# CoilDriver.net
KiCad netlist of a schematic drawn in Altium Designer
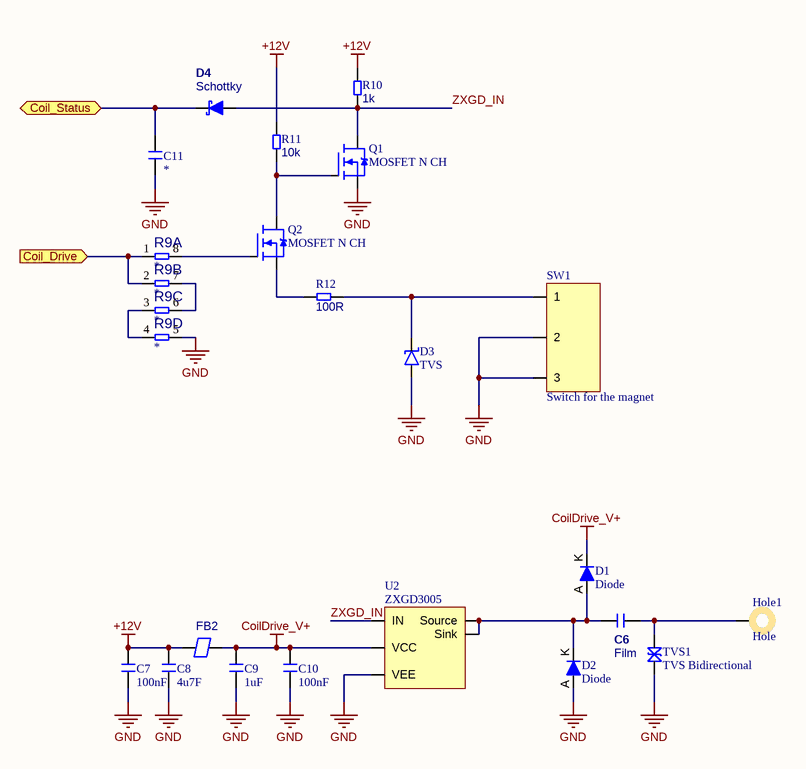
[diagram p0: CoilDriver.SchDoc]

(export (version "E")
  (design (tool "Eeschema 10.0.6"))
  (components
    (comp (ref "C6")
      (value "Film")
      (footprint "Cap Film 5mm pitch, 7.2x7.2mm")
      (libsource (lib "wes") (part "Capacitor - Film"))
    )
    (comp (ref "C7")
      (value "100nF")
      (footprint "C0603_N")
      (description "Capacitor MLCC")
      (fields
        (field (name "MANUFACTURER") "Yageo")
        (field (name "MANUFACTURER PART NUMBER") "CC0603KRX7R9BB104")
      )
      (libsource (lib "wes") (part "Capacitor"))
    )
    (comp (ref "C8")
      (value "4u7F")
      (footprint "C1206_N")
      (description "Capacitor MLCC")
      (fields
        (field (name "MANUFACTURER") "Yageo")
        (field (name "MANUFACTURER PART NUMBER") "CC0603KRX7R9BB104")
      )
      (libsource (lib "wes") (part "Capacitor"))
    )
    (comp (ref "C9")
      (value "1uF")
      (footprint "C0603_N")
      (description "Capacitor MLCC")
      (fields
        (field (name "MANUFACTURER") "Yageo")
        (field (name "MANUFACTURER PART NUMBER") "CC0603KRX7R9BB104")
      )
      (libsource (lib "wes") (part "Capacitor"))
    )
    (comp (ref "C10")
      (value "100nF")
      (footprint "C0603_N")
      (description "Capacitor MLCC")
      (fields
        (field (name "MANUFACTURER") "Yageo")
        (field (name "MANUFACTURER PART NUMBER") "CC0603KRX7R9BB104")
      )
      (libsource (lib "wes") (part "Capacitor"))
    )
    (comp (ref "C11")
      (value "*")
      (footprint "C0603_N")
      (description "Capacitor MLCC")
      (fields
        (field (name "MANUFACTURER") "Yageo")
        (field (name "MANUFACTURER PART NUMBER") "CC0603KRX7R9BB104")
      )
      (libsource (lib "wes") (part "Capacitor"))
    )
    (comp (ref "D1") (value "Diode") (footprint "SOD323F") (libsource (lib "wes") (part "Diode")))
    (comp (ref "D2") (value "Diode") (footprint "SOD323F") (libsource (lib "wes") (part "Diode")))
    (comp (ref "D3") (value "TVS") (footprint "SOD323F-Comchip Variant") (libsource (lib "wes") (part "TVS")))
    (comp (ref "D4") (value "Schottky") (footprint "SOD323F") (libsource (lib "wes") (part "Diode Schottky")))
    (comp (ref "FB2")
      (value "Ferrite Bead")
      (footprint "F0603_N")
      (libsource (lib "wes") (part "Ferrite Bead"))
    )
    (comp (ref "Hole1")
      (value "Hole")
      (footprint "Insert-Thread-SMD-M2")
      (libsource (lib "wes") (part "Hole"))
    )
    (comp (ref "Q1") (value "MOSFET N CH") (footprint "SOT23_N") (libsource (lib "wes") (part "MOSFET N CH")))
    (comp (ref "Q2") (value "MOSFET N CH") (footprint "SOT23_N") (libsource (lib "wes") (part "MOSFET N CH")))
    (comp (ref "R9")
      (value "Resistor Array - 4P")
      (footprint "YC164")
      (fields (field (name "ALTIUM_VALUE") "*"))
      (libsource (lib "wes") (part "Resistor Array - 4P"))
    )
    (comp (ref "R10")
      (value "1k")
      (footprint "R0603")
      (fields (field (name "Comment") "Resistor") (field (name "PUBLISHER") "Altium Limited"))
      (libsource (lib "wes") (part "Resistor"))
    )
    (comp (ref "R11")
      (value "10k")
      (footprint "R0603")
      (fields (field (name "Comment") "Resistor") (field (name "PUBLISHER") "Altium Limited"))
      (libsource (lib "wes") (part "Resistor"))
    )
    (comp (ref "R12")
      (value "100R")
      (footprint "R0603")
      (fields (field (name "Comment") "Resistor") (field (name "PUBLISHER") "Altium Limited"))
      (libsource (lib "wes") (part "Resistor"))
    )
    (comp (ref "SW1")
      (value "Switch for the magnet")
      (footprint "Linobyte - MagnetSwitch")
      (libsource (lib "wes") (part "Linobyte - MagnetSwitch"))
    )
    (comp (ref "TVS1")
      (value "TVS Bidirectional")
      (footprint "DO214AC SMA")
      (libsource (lib "wes") (part "TVS Bidirectional"))
    )
    (comp (ref "U2") (value "ZXGD3005") (footprint "SOT23-6_N") (libsource (lib "wes") (part "ZXGD3005")))
  )
  (nets
    (net (code "1") (name "+12V") (class "Default")
      (node (ref "C7") (pin "1") (pintype "passive"))
      (node (ref "C8") (pin "1") (pintype "passive"))
      (node (ref "FB2") (pin "2") (pinfunction "2_2") (pintype "passive"))
      (node (ref "R10") (pin "2") (pinfunction "2_2") (pintype "passive"))
      (node (ref "R11") (pin "2") (pinfunction "2_2") (pintype "passive"))
    )
    (net (code "2") (name "/Coil_Drive") (class "Default")
      (node (ref "R9") (pin "1") (pinfunction "1_1") (pintype "passive"))
      (node (ref "R9") (pin "2") (pinfunction "2_2") (pintype "passive"))
    )
    (net (code "3") (name "/Coil_Status") (class "Default")
      (node (ref "C11") (pin "1") (pintype "passive"))
      (node (ref "D4") (pin "K") (pinfunction "K_K") (pintype "passive"))
    )
    (net (code "4") (name "/ZXGD_IN") (class "Default")
      (node (ref "D4") (pin "A") (pinfunction "A_A") (pintype "passive"))
      (node (ref "Q1") (pin "2") (pinfunction "D_2") (pintype "passive"))
      (node (ref "R10") (pin "1") (pinfunction "1_1") (pintype "passive"))
      (node (ref "U2") (pin "2") (pinfunction "IN_2") (pintype "passive"))
    )
    (net (code "5") (name "CoilDrive_V+") (class "Default")
      (node (ref "C10") (pin "1") (pintype "passive"))
      (node (ref "C9") (pin "1") (pintype "passive"))
      (node (ref "D1") (pin "K") (pinfunction "K_K") (pintype "passive"))
      (node (ref "FB2") (pin "1") (pinfunction "1_1") (pintype "passive"))
      (node (ref "U2") (pin "1") (pinfunction "VCC_1") (pintype "passive"))
    )
    (net (code "6") (name "GND") (class "Default")
      (node (ref "C10") (pin "2") (pintype "passive"))
      (node (ref "C11") (pin "2") (pintype "passive"))
      (node (ref "C7") (pin "2") (pintype "passive"))
      (node (ref "C8") (pin "2") (pintype "passive"))
      (node (ref "C9") (pin "2") (pintype "passive"))
      (node (ref "D2") (pin "A") (pinfunction "A_A") (pintype "passive"))
      (node (ref "D3") (pin "1") (pinfunction "1_1") (pintype "passive"))
      (node (ref "Q1") (pin "3") (pinfunction "S_3") (pintype "passive"))
      (node (ref "R9") (pin "5") (pinfunction "5_5") (pintype "passive"))
      (node (ref "SW1") (pin "2") (pinfunction "2_2") (pintype "passive"))
      (node (ref "SW1") (pin "3") (pinfunction "3_3") (pintype "passive"))
      (node (ref "TVS1") (pin "2") (pinfunction "2_2") (pintype "passive"))
      (node (ref "U2") (pin "3") (pinfunction "VEE_3") (pintype "passive"))
    )
    (net (code "7") (name "Net-(C6-Pad1)") (class "Default")
      (node (ref "C6") (pin "1") (pintype "passive"))
      (node (ref "Hole1") (pin "1") (pinfunction "1_1") (pintype "passive"))
      (node (ref "TVS1") (pin "1") (pinfunction "1_1") (pintype "passive"))
    )
    (net (code "8") (name "Net-(D3-Pad2)") (class "Default")
      (node (ref "D3") (pin "2") (pinfunction "2_2") (pintype "passive"))
      (node (ref "R12") (pin "2") (pinfunction "2_2") (pintype "passive"))
      (node (ref "SW1") (pin "1") (pinfunction "1_1") (pintype "passive"))
    )
    (net (code "9") (name "Net-(Q1-G)") (class "Default")
      (node (ref "Q1") (pin "1") (pinfunction "G_1") (pintype "passive"))
      (node (ref "Q2") (pin "2") (pinfunction "D_2") (pintype "passive"))
      (node (ref "R11") (pin "1") (pinfunction "1_1") (pintype "passive"))
    )
    (net (code "10") (name "Net-(Q2-G)") (class "Default")
      (node (ref "Q2") (pin "1") (pinfunction "G_1") (pintype "passive"))
      (node (ref "R9") (pin "8") (pinfunction "8_8") (pintype "passive"))
    )
    (net (code "11") (name "Net-(Q2-S)") (class "Default")
      (node (ref "Q2") (pin "3") (pinfunction "S_3") (pintype "passive"))
      (node (ref "R12") (pin "1") (pinfunction "1_1") (pintype "passive"))
    )
    (net (code "12") (name "Net-(R9-Pad3)") (class "Default")
      (node (ref "R9") (pin "3") (pinfunction "3_3") (pintype "passive"))
      (node (ref "R9") (pin "4") (pinfunction "4_4") (pintype "passive"))
    )
    (net (code "13") (name "Net-(R9-Pad6)") (class "Default")
      (node (ref "R9") (pin "6") (pinfunction "6_6") (pintype "passive"))
      (node (ref "R9") (pin "7") (pinfunction "7_7") (pintype "passive"))
    )
    (net (code "14") (name "Net-(U2-Sink)") (class "Default")
      (node (ref "C6") (pin "2") (pintype "passive"))
      (node (ref "D1") (pin "A") (pinfunction "A_A") (pintype "passive"))
      (node (ref "D2") (pin "K") (pinfunction "K_K") (pintype "passive"))
      (node (ref "U2") (pin "4") (pinfunction "Sink_4") (pintype "passive"))
      (node (ref "U2") (pin "6") (pinfunction "Source_6") (pintype "passive"))
    )
  )
)
